# Main.net
KiCad netlist of a schematic drawn in Altium Designer
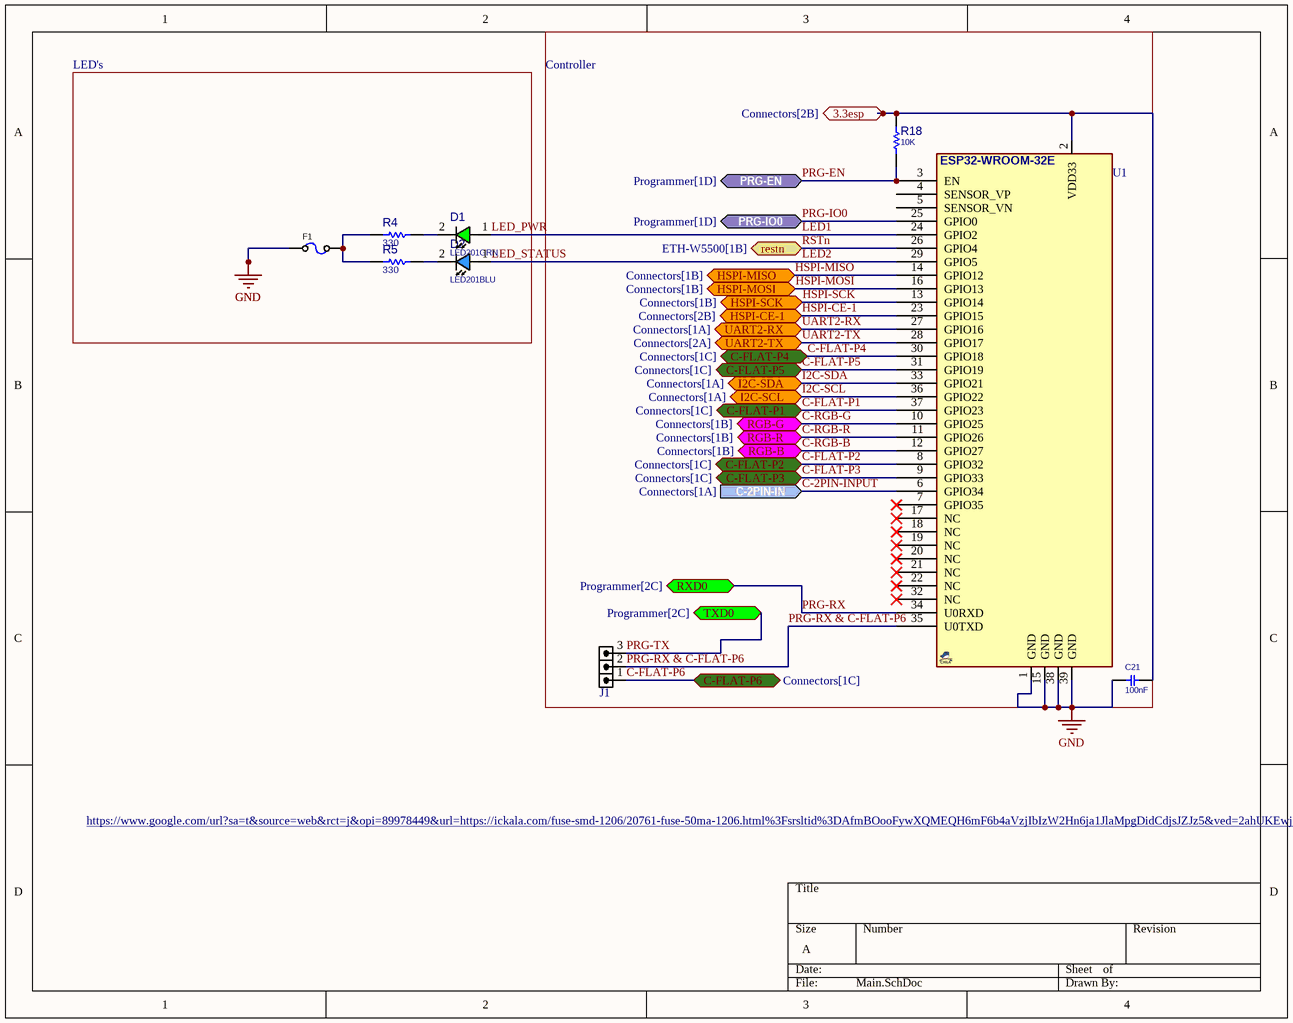
[diagram p0: Main.SchDoc]

(export (version "E")
  (design (tool "Eeschema 10.0.6"))
  (components
    (comp (ref "C21")
      (value "100nF")
      (footprint "C_CERM_D3")
      (description "CAP, THD, CER MULTI LAYER,")
      (fields (field (name "MANF_P#") "MANF_PART#") (field (name "MANF") "MANF"))
      (libsource (lib "passive_thd") (part "CAP_THD_CER"))
    )
    (comp (ref "D1")
      (value "LED201GRN")
      (footprint "LED0201GRN")
      (description "LED, SMD, 0201, GREEN")
      (fields (field (name "MANF") "Kingbright") (field (name "MANF_P#") "APG0603CGC"))
      (libsource (lib "led(diode)") (part "LED_SMD_0201_GRN"))
    )
    (comp (ref "D2")
      (value "LED201BLU")
      (footprint "LED0201BLU")
      (description "LED, SMD, 0201, BLUE")
      (fields (field (name "MANF") "Lumex") (field (name "MANF_P#") "SML-LX0201USBC-TR"))
      (libsource (lib "led(diode)") (part "LED_SMD_0201_BLU"))
    )
    (comp (ref "F1")
      (value "~")
      (footprint "F1206")
      (description "Fuse, 160mA, 63VDC, 1206, SMD, Fast Acting")
      (fields (field (name "MANF") "Holly Fuse") (field (name "MANF_P#") "12T-0160L"))
      (libsource (lib "protect_tvs_esd_fuse") (part "FUSE_160mA_1206"))
    )
    (comp (ref "J1")
      (value "HDRM3")
      (footprint "HDR_M_1X3")
      (description "CONN, HEADER, Male, pitch: 2.54mm, 3POS")
      (libsource (lib "conn_header_2.54mm_st") (part "HDR_M_1X3"))
    )
    (comp (ref "R4")
      (value "330")
      (footprint "R0402")
      (description "RESISTOR, SMD")
      (libsource (lib "passive_smd") (part "RES_SMD"))
    )
    (comp (ref "R5")
      (value "330")
      (footprint "R0402")
      (description "RESISTOR, SMD")
      (libsource (lib "passive_smd") (part "RES_SMD"))
    )
    (comp (ref "R18")
      (value "10K")
      (footprint "R025W_AX04")
      (description "RESISTOR, THD")
      (fields (field (name "MANF_P#") "RK73H1ETTP4701F") (field (name "MANF") "KOA SPEER"))
      (libsource (lib "passive_thd") (part "RES_THD"))
    )
    (comp (ref "U1")
      (value "ESP32-WROOM-32E")
      (footprint "ESP32S")
      (description "WiFi with Bluetooth 4.0")
      (libsource (lib "module_wifi") (part "ESP32-WROOM-32E"))
    )
  )
  (nets
    (net (code "1") (name "/3.3esp") (class "Default")
      (node (ref "C21") (pin "2") (pinfunction "2_2") (pintype "passive"))
      (node (ref "R18") (pin "2") (pinfunction "2_2") (pintype "passive"))
      (node (ref "U1") (pin "2") (pinfunction "VDD33_2") (pintype "passive"))
    )
    (net (code "2") (name "/C-2PIN-INPUT") (class "Default")
      (node (ref "U1") (pin "6") (pinfunction "GPIO34_6") (pintype "passive"))
    )
    (net (code "3") (name "/C-FLAT-P1") (class "Default")
      (node (ref "U1") (pin "37") (pinfunction "GPIO23_37") (pintype "passive"))
    )
    (net (code "4") (name "/C-FLAT-P2") (class "Default")
      (node (ref "U1") (pin "8") (pinfunction "GPIO32_8") (pintype "passive"))
    )
    (net (code "5") (name "/C-FLAT-P3") (class "Default")
      (node (ref "U1") (pin "9") (pinfunction "GPIO33_9") (pintype "passive"))
    )
    (net (code "6") (name "/C-FLAT-P4") (class "Default")
      (node (ref "U1") (pin "30") (pinfunction "GPIO18_30") (pintype "passive"))
    )
    (net (code "7") (name "/C-FLAT-P5") (class "Default")
      (node (ref "U1") (pin "31") (pinfunction "GPIO19_31") (pintype "passive"))
    )
    (net (code "8") (name "/C-FLAT-P6") (class "Default")
      (node (ref "J1") (pin "1") (pinfunction "1_1") (pintype "passive"))
    )
    (net (code "9") (name "/C-RGB-B") (class "Default")
      (node (ref "U1") (pin "12") (pinfunction "GPIO27_12") (pintype "passive"))
    )
    (net (code "10") (name "/C-RGB-G") (class "Default")
      (node (ref "U1") (pin "10") (pinfunction "GPIO25_10") (pintype "passive"))
    )
    (net (code "11") (name "/C-RGB-R") (class "Default")
      (node (ref "U1") (pin "11") (pinfunction "GPIO26_11") (pintype "passive"))
    )
    (net (code "12") (name "/HSPI-CE-1") (class "Default")
      (node (ref "U1") (pin "23") (pinfunction "GPIO15_23") (pintype "passive"))
    )
    (net (code "13") (name "/HSPI-MISO") (class "Default")
      (node (ref "U1") (pin "14") (pinfunction "GPIO12_14") (pintype "passive"))
    )
    (net (code "14") (name "/HSPI-MOSI") (class "Default")
      (node (ref "U1") (pin "16") (pinfunction "GPIO13_16") (pintype "passive"))
    )
    (net (code "15") (name "/HSPI-SCK") (class "Default")
      (node (ref "U1") (pin "13") (pinfunction "GPIO14_13") (pintype "passive"))
    )
    (net (code "16") (name "/I2C-SCL") (class "Default")
      (node (ref "U1") (pin "36") (pinfunction "GPIO22_36") (pintype "passive"))
    )
    (net (code "17") (name "/I2C-SDA") (class "Default")
      (node (ref "U1") (pin "33") (pinfunction "GPIO21_33") (pintype "passive"))
    )
    (net (code "18") (name "/LED1") (class "Default")
      (node (ref "D1") (pin "1") (pinfunction "ANODE_1") (pintype "passive"))
      (node (ref "U1") (pin "24") (pinfunction "GPIO2_24") (pintype "passive"))
    )
    (net (code "19") (name "/LED2") (class "Default")
      (node (ref "D2") (pin "1") (pinfunction "ANODE_1") (pintype "passive"))
      (node (ref "U1") (pin "29") (pinfunction "GPIO5_29") (pintype "passive"))
    )
    (net (code "20") (name "/PRG-EN") (class "Default")
      (node (ref "R18") (pin "1") (pinfunction "1_1") (pintype "passive"))
      (node (ref "U1") (pin "3") (pinfunction "EN_3") (pintype "passive"))
    )
    (net (code "21") (name "/PRG-IO0") (class "Default")
      (node (ref "U1") (pin "25") (pinfunction "GPIO0_25") (pintype "passive"))
    )
    (net (code "22") (name "/PRG-RX") (class "Default")
      (node (ref "U1") (pin "34") (pinfunction "U0RXD_34") (pintype "passive"))
    )
    (net (code "23") (name "/PRG-RX & C-FLAT-P6") (class "Default")
      (node (ref "J1") (pin "2") (pinfunction "2_2") (pintype "passive"))
      (node (ref "U1") (pin "35") (pinfunction "U0TXD_35") (pintype "passive"))
    )
    (net (code "24") (name "/PRG-TX") (class "Default")
      (node (ref "J1") (pin "3") (pinfunction "3_3") (pintype "passive"))
    )
    (net (code "25") (name "/RSTn") (class "Default")
      (node (ref "U1") (pin "26") (pinfunction "GPIO4_26") (pintype "passive"))
    )
    (net (code "26") (name "/UART2-RX") (class "Default")
      (node (ref "U1") (pin "27") (pinfunction "GPIO16_27") (pintype "passive"))
    )
    (net (code "27") (name "/UART2-TX") (class "Default")
      (node (ref "U1") (pin "28") (pinfunction "GPIO17_28") (pintype "passive"))
    )
    (net (code "28") (name "GND") (class "Default")
      (node (ref "C21") (pin "1") (pinfunction "1_1") (pintype "passive"))
      (node (ref "F1") (pin "1") (pinfunction "1_1") (pintype "passive"))
      (node (ref "U1") (pin "1") (pinfunction "GND_1") (pintype "passive"))
      (node (ref "U1") (pin "15") (pinfunction "GND_15") (pintype "passive"))
      (node (ref "U1") (pin "38") (pinfunction "GND_38") (pintype "passive"))
      (node (ref "U1") (pin "39") (pinfunction "GND_39") (pintype "passive"))
    )
    (net (code "29") (name "Net-(D1-CATHODE)") (class "Default")
      (node (ref "D1") (pin "2") (pinfunction "CATHODE_2") (pintype "passive"))
      (node (ref "R4") (pin "2") (pinfunction "2_2") (pintype "passive"))
    )
    (net (code "30") (name "Net-(D2-CATHODE)") (class "Default")
      (node (ref "D2") (pin "2") (pinfunction "CATHODE_2") (pintype "passive"))
      (node (ref "R5") (pin "2") (pinfunction "2_2") (pintype "passive"))
    )
    (net (code "31") (name "Net-(F1-Pad2)") (class "Default")
      (node (ref "F1") (pin "2") (pinfunction "2_2") (pintype "passive"))
      (node (ref "R4") (pin "1") (pinfunction "1_1") (pintype "passive"))
      (node (ref "R5") (pin "1") (pinfunction "1_1") (pintype "passive"))
    )
    (net (code "32") (name "unconnected-(U1-GPIO35-Pad7)") (class "Default")
      (node (ref "U1") (pin "7") (pinfunction "GPIO35_7") (pintype "passive+no_connect"))
    )
    (net (code "33") (name "unconnected-(U1-NC-Pad17)") (class "Default")
      (node (ref "U1") (pin "17") (pinfunction "NC_17") (pintype "passive+no_connect"))
    )
    (net (code "34") (name "unconnected-(U1-NC-Pad18)") (class "Default")
      (node (ref "U1") (pin "18") (pinfunction "NC_18") (pintype "passive+no_connect"))
    )
    (net (code "35") (name "unconnected-(U1-NC-Pad19)") (class "Default")
      (node (ref "U1") (pin "19") (pinfunction "NC_19") (pintype "passive+no_connect"))
    )
    (net (code "36") (name "unconnected-(U1-NC-Pad20)") (class "Default")
      (node (ref "U1") (pin "20") (pinfunction "NC_20") (pintype "passive+no_connect"))
    )
    (net (code "37") (name "unconnected-(U1-NC-Pad21)") (class "Default")
      (node (ref "U1") (pin "21") (pinfunction "NC_21") (pintype "passive+no_connect"))
    )
    (net (code "38") (name "unconnected-(U1-NC-Pad22)") (class "Default")
      (node (ref "U1") (pin "22") (pinfunction "NC_22") (pintype "passive+no_connect"))
    )
    (net (code "39") (name "unconnected-(U1-NC-Pad32)") (class "Default")
      (node (ref "U1") (pin "32") (pinfunction "NC_32") (pintype "passive+no_connect"))
    )
    (net (code "40") (name "unconnected-(U1-SENSOR_VN-Pad5)") (class "Default")
      (node (ref "U1") (pin "5") (pinfunction "SENSOR_VN_5") (pintype "passive"))
    )
    (net (code "41") (name "unconnected-(U1-SENSOR_VP-Pad4)") (class "Default")
      (node (ref "U1") (pin "4") (pinfunction "SENSOR_VP_4") (pintype "passive"))
    )
  )
)
